# ANS_1_1.net
KiCad netlist of a schematic drawn in EAGLE
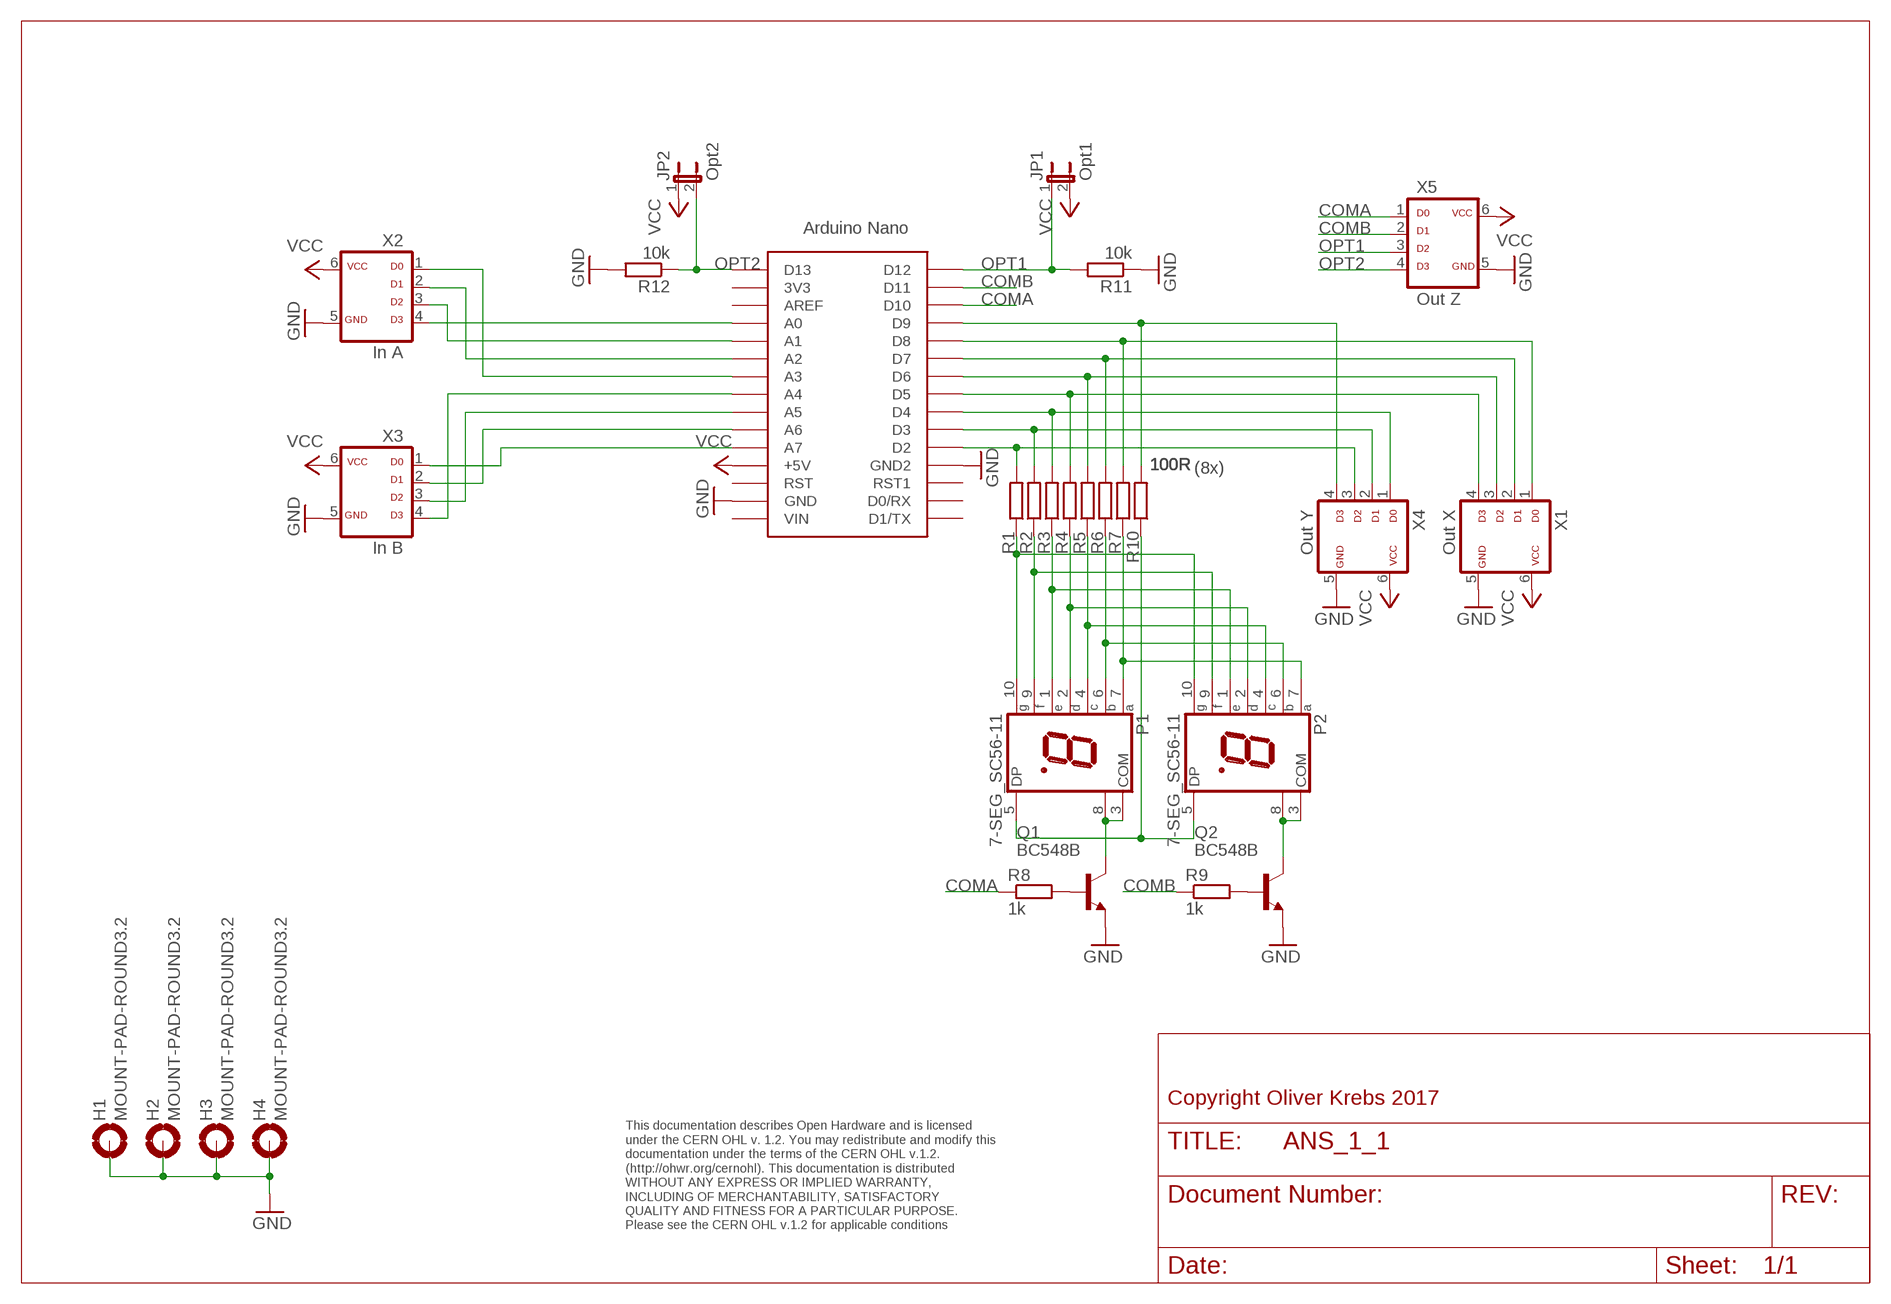
[diagram p0: schematic, sheet 1]

(export (version "E")
  (design (tool "Eeschema 10.0.6"))
  (components
    (comp (ref "H1")
      (value "MOUNT-PAD-ROUND3.2")
      (footprint "eagle-import:3,2-PAD")
      (libsource (lib "eagle-import") (part "MOUNT-PAD-ROUND3.2"))
    )
    (comp (ref "H2")
      (value "MOUNT-PAD-ROUND3.2")
      (footprint "eagle-import:3,2-PAD")
      (libsource (lib "eagle-import") (part "MOUNT-PAD-ROUND3.2"))
    )
    (comp (ref "H3")
      (value "MOUNT-PAD-ROUND3.2")
      (footprint "eagle-import:3,2-PAD")
      (libsource (lib "eagle-import") (part "MOUNT-PAD-ROUND3.2"))
    )
    (comp (ref "H4")
      (value "MOUNT-PAD-ROUND3.2")
      (footprint "eagle-import:3,2-PAD")
      (libsource (lib "eagle-import") (part "MOUNT-PAD-ROUND3.2"))
    )
    (comp (ref "JP1")
      (value "Opt1")
      (footprint "eagle-import:JP1")
      (libsource (lib "eagle-import") (part "JP1E"))
    )
    (comp (ref "JP2")
      (value "Opt2")
      (footprint "eagle-import:JP1")
      (libsource (lib "eagle-import") (part "JP1E"))
    )
    (comp (ref "P1")
      (value "7-SEG_SC56-11")
      (footprint "eagle-import:SA56-11")
      (libsource (lib "eagle-import") (part "7-SEG_SA56-11"))
    )
    (comp (ref "P2")
      (value "7-SEG_SC56-11")
      (footprint "eagle-import:SA56-11")
      (libsource (lib "eagle-import") (part "7-SEG_SA56-11"))
    )
    (comp (ref "Q1")
      (value "BC548B")
      (footprint "eagle-import:TO92-EBC")
      (libsource (lib "eagle-import") (part "BC548B"))
    )
    (comp (ref "Q2")
      (value "BC548B")
      (footprint "eagle-import:TO92-EBC")
      (libsource (lib "eagle-import") (part "BC548B"))
    )
    (comp (ref "R1")
      (value "100R")
      (footprint "eagle-import:0207_10")
      (libsource (lib "eagle-import") (part "R-EU_0207/10"))
    )
    (comp (ref "R2")
      (value "100R")
      (footprint "eagle-import:0207_10")
      (libsource (lib "eagle-import") (part "R-EU_0207/10"))
    )
    (comp (ref "R3")
      (value "100R")
      (footprint "eagle-import:0207_10")
      (libsource (lib "eagle-import") (part "R-EU_0207/10"))
    )
    (comp (ref "R4")
      (value "100R")
      (footprint "eagle-import:0207_10")
      (libsource (lib "eagle-import") (part "R-EU_0207/10"))
    )
    (comp (ref "R5")
      (value "100R")
      (footprint "eagle-import:0207_10")
      (libsource (lib "eagle-import") (part "R-EU_0207/10"))
    )
    (comp (ref "R6")
      (value "100R")
      (footprint "eagle-import:0207_10")
      (libsource (lib "eagle-import") (part "R-EU_0207/10"))
    )
    (comp (ref "R7")
      (value "100R")
      (footprint "eagle-import:0207_10")
      (libsource (lib "eagle-import") (part "R-EU_0207/10"))
    )
    (comp (ref "R8")
      (value "1k")
      (footprint "eagle-import:0207_10")
      (libsource (lib "eagle-import") (part "R-EU_0207/10"))
    )
    (comp (ref "R9")
      (value "1k")
      (footprint "eagle-import:0207_10")
      (libsource (lib "eagle-import") (part "R-EU_0207/10"))
    )
    (comp (ref "R10")
      (value "100R")
      (footprint "eagle-import:0207_10")
      (libsource (lib "eagle-import") (part "R-EU_0207/10"))
    )
    (comp (ref "R11")
      (value "10k")
      (footprint "eagle-import:0207_10")
      (libsource (lib "eagle-import") (part "R-EU_0207/10"))
    )
    (comp (ref "R12")
      (value "10k")
      (footprint "eagle-import:0207_10")
      (libsource (lib "eagle-import") (part "R-EU_0207/10"))
    )
    (comp (ref "U$1")
      (value "NANO")
      (footprint "eagle-import:NANO")
      (libsource (lib "eagle-import") (part "NANO"))
    )
    (comp (ref "X1")
      (value "Out X")
      (footprint "eagle-import:ML-6")
      (libsource (lib "eagle-import") (part "ML6D"))
    )
    (comp (ref "X2")
      (value "In A")
      (footprint "eagle-import:ML-6")
      (libsource (lib "eagle-import") (part "ML6D"))
    )
    (comp (ref "X3")
      (value "In B")
      (footprint "eagle-import:ML-6")
      (libsource (lib "eagle-import") (part "ML6D"))
    )
    (comp (ref "X4")
      (value "Out Y")
      (footprint "eagle-import:ML-6")
      (libsource (lib "eagle-import") (part "ML6D"))
    )
    (comp (ref "X5")
      (value "Out Z")
      (footprint "eagle-import:ML-6")
      (libsource (lib "eagle-import") (part "ML6D"))
    )
  )
  (nets
    (net (code "1") (name "/COMA") (class "Default")
      (node (ref "R8") (pin "1") (pinfunction "1_1") (pintype "passive"))
      (node (ref "U$1") (pin "D10") (pinfunction "D10_D10") (pintype "bidirectional"))
      (node (ref "X5") (pin "1") (pinfunction "1_1") (pintype "passive"))
    )
    (net (code "2") (name "/COMB") (class "Default")
      (node (ref "R9") (pin "1") (pinfunction "1_1") (pintype "passive"))
      (node (ref "U$1") (pin "D11") (pinfunction "D11_D11") (pintype "bidirectional"))
      (node (ref "X5") (pin "2") (pinfunction "2_2") (pintype "passive"))
    )
    (net (code "3") (name "/OPT1") (class "Default")
      (node (ref "JP1") (pin "1") (pinfunction "1_1") (pintype "passive"))
      (node (ref "R11") (pin "2") (pinfunction "2_2") (pintype "passive"))
      (node (ref "U$1") (pin "D12") (pinfunction "D12_D12") (pintype "bidirectional"))
      (node (ref "X5") (pin "3") (pinfunction "3_3") (pintype "passive"))
    )
    (net (code "4") (name "/OPT2") (class "Default")
      (node (ref "JP2") (pin "2") (pinfunction "2_2") (pintype "passive"))
      (node (ref "R12") (pin "1") (pinfunction "1_1") (pintype "passive"))
      (node (ref "U$1") (pin "D13") (pinfunction "D13_D13") (pintype "bidirectional"))
      (node (ref "X5") (pin "4") (pinfunction "4_4") (pintype "passive"))
    )
    (net (code "5") (name "GND") (class "Default")
      (node (ref "H1") (pin "B3,2") (pinfunction "MOUNT_B3,2") (pintype "passive"))
      (node (ref "H2") (pin "B3,2") (pinfunction "MOUNT_B3,2") (pintype "passive"))
      (node (ref "H3") (pin "B3,2") (pinfunction "MOUNT_B3,2") (pintype "passive"))
      (node (ref "H4") (pin "B3,2") (pinfunction "MOUNT_B3,2") (pintype "passive"))
      (node (ref "Q1") (pin "E") (pinfunction "E_E") (pintype "passive"))
      (node (ref "Q2") (pin "E") (pinfunction "E_E") (pintype "passive"))
      (node (ref "R11") (pin "1") (pinfunction "1_1") (pintype "passive"))
      (node (ref "R12") (pin "2") (pinfunction "2_2") (pintype "passive"))
      (node (ref "U$1") (pin "GND") (pinfunction "GND_GND") (pintype "bidirectional"))
      (node (ref "U$1") (pin "GND1") (pinfunction "GND2_GND1") (pintype "bidirectional"))
      (node (ref "X1") (pin "5") (pinfunction "5_5") (pintype "passive"))
      (node (ref "X2") (pin "5") (pinfunction "5_5") (pintype "passive"))
      (node (ref "X3") (pin "5") (pinfunction "5_5") (pintype "passive"))
      (node (ref "X4") (pin "5") (pinfunction "5_5") (pintype "passive"))
      (node (ref "X5") (pin "5") (pinfunction "5_5") (pintype "passive"))
    )
    (net (code "6") (name "Net-(P1-A)") (class "Default")
      (node (ref "P1") (pin "7") (pinfunction "A_7") (pintype "passive"))
      (node (ref "P2") (pin "7") (pinfunction "A_7") (pintype "passive"))
      (node (ref "R7") (pin "1") (pinfunction "1_1") (pintype "passive"))
    )
    (net (code "7") (name "Net-(P1-B)") (class "Default")
      (node (ref "P1") (pin "6") (pinfunction "B_6") (pintype "passive"))
      (node (ref "P2") (pin "6") (pinfunction "B_6") (pintype "passive"))
      (node (ref "R6") (pin "1") (pinfunction "1_1") (pintype "passive"))
    )
    (net (code "8") (name "Net-(P1-C)") (class "Default")
      (node (ref "P1") (pin "4") (pinfunction "C_4") (pintype "passive"))
      (node (ref "P2") (pin "4") (pinfunction "C_4") (pintype "passive"))
      (node (ref "R5") (pin "1") (pinfunction "1_1") (pintype "passive"))
    )
    (net (code "9") (name "Net-(P1-COM-Pad3)") (class "Default")
      (node (ref "P1") (pin "3") (pinfunction "COM_3") (pintype "passive"))
      (node (ref "P1") (pin "8") (pinfunction "COM_8") (pintype "passive"))
      (node (ref "Q1") (pin "C") (pinfunction "C_C") (pintype "passive"))
    )
    (net (code "10") (name "Net-(P1-D)") (class "Default")
      (node (ref "P1") (pin "2") (pinfunction "D_2") (pintype "passive"))
      (node (ref "P2") (pin "2") (pinfunction "D_2") (pintype "passive"))
      (node (ref "R4") (pin "1") (pinfunction "1_1") (pintype "passive"))
    )
    (net (code "11") (name "Net-(P1-DP)") (class "Default")
      (node (ref "P1") (pin "5") (pinfunction "DP_5") (pintype "passive"))
      (node (ref "P2") (pin "5") (pinfunction "DP_5") (pintype "passive"))
      (node (ref "R10") (pin "1") (pinfunction "1_1") (pintype "passive"))
    )
    (net (code "12") (name "Net-(P1-E)") (class "Default")
      (node (ref "P1") (pin "1") (pinfunction "E_1") (pintype "passive"))
      (node (ref "P2") (pin "1") (pinfunction "E_1") (pintype "passive"))
      (node (ref "R3") (pin "1") (pinfunction "1_1") (pintype "passive"))
    )
    (net (code "13") (name "Net-(P1-F)") (class "Default")
      (node (ref "P1") (pin "9") (pinfunction "F_9") (pintype "passive"))
      (node (ref "P2") (pin "9") (pinfunction "F_9") (pintype "passive"))
      (node (ref "R2") (pin "1") (pinfunction "1_1") (pintype "passive"))
    )
    (net (code "14") (name "Net-(P1-G)") (class "Default")
      (node (ref "P1") (pin "10") (pinfunction "G_10") (pintype "passive"))
      (node (ref "P2") (pin "10") (pinfunction "G_10") (pintype "passive"))
      (node (ref "R1") (pin "1") (pinfunction "1_1") (pintype "passive"))
    )
    (net (code "15") (name "Net-(P2-COM-Pad3)") (class "Default")
      (node (ref "P2") (pin "3") (pinfunction "COM_3") (pintype "passive"))
      (node (ref "P2") (pin "8") (pinfunction "COM_8") (pintype "passive"))
      (node (ref "Q2") (pin "C") (pinfunction "C_C") (pintype "passive"))
    )
    (net (code "16") (name "Net-(Q1-PadB)") (class "Default")
      (node (ref "Q1") (pin "B") (pinfunction "B_B") (pintype "passive"))
      (node (ref "R8") (pin "2") (pinfunction "2_2") (pintype "passive"))
    )
    (net (code "17") (name "Net-(Q2-PadB)") (class "Default")
      (node (ref "Q2") (pin "B") (pinfunction "B_B") (pintype "passive"))
      (node (ref "R9") (pin "2") (pinfunction "2_2") (pintype "passive"))
    )
    (net (code "18") (name "Net-(R1-Pad2)") (class "Default")
      (node (ref "R1") (pin "2") (pinfunction "2_2") (pintype "passive"))
      (node (ref "U$1") (pin "D2") (pinfunction "D2_D2") (pintype "bidirectional"))
      (node (ref "X4") (pin "3") (pinfunction "3_3") (pintype "passive"))
    )
    (net (code "19") (name "Net-(R2-Pad2)") (class "Default")
      (node (ref "R2") (pin "2") (pinfunction "2_2") (pintype "passive"))
      (node (ref "U$1") (pin "D3") (pinfunction "D3_D3") (pintype "bidirectional"))
      (node (ref "X4") (pin "2") (pinfunction "2_2") (pintype "passive"))
    )
    (net (code "20") (name "Net-(R3-Pad2)") (class "Default")
      (node (ref "R3") (pin "2") (pinfunction "2_2") (pintype "passive"))
      (node (ref "U$1") (pin "D4") (pinfunction "D4_D4") (pintype "bidirectional"))
      (node (ref "X4") (pin "1") (pinfunction "1_1") (pintype "passive"))
    )
    (net (code "21") (name "Net-(R4-Pad2)") (class "Default")
      (node (ref "R4") (pin "2") (pinfunction "2_2") (pintype "passive"))
      (node (ref "U$1") (pin "D5") (pinfunction "D5_D5") (pintype "bidirectional"))
      (node (ref "X1") (pin "4") (pinfunction "4_4") (pintype "passive"))
    )
    (net (code "22") (name "Net-(R5-Pad2)") (class "Default")
      (node (ref "R5") (pin "2") (pinfunction "2_2") (pintype "passive"))
      (node (ref "U$1") (pin "D6") (pinfunction "D6_D6") (pintype "bidirectional"))
      (node (ref "X1") (pin "3") (pinfunction "3_3") (pintype "passive"))
    )
    (net (code "23") (name "Net-(R6-Pad2)") (class "Default")
      (node (ref "R6") (pin "2") (pinfunction "2_2") (pintype "passive"))
      (node (ref "U$1") (pin "D7") (pinfunction "D7_D7") (pintype "bidirectional"))
      (node (ref "X1") (pin "2") (pinfunction "2_2") (pintype "passive"))
    )
    (net (code "24") (name "Net-(R7-Pad2)") (class "Default")
      (node (ref "R7") (pin "2") (pinfunction "2_2") (pintype "passive"))
      (node (ref "U$1") (pin "D8") (pinfunction "D8_D8") (pintype "bidirectional"))
      (node (ref "X1") (pin "1") (pinfunction "1_1") (pintype "passive"))
    )
    (net (code "25") (name "Net-(R10-Pad2)") (class "Default")
      (node (ref "R10") (pin "2") (pinfunction "2_2") (pintype "passive"))
      (node (ref "U$1") (pin "D9") (pinfunction "D9_D9") (pintype "bidirectional"))
      (node (ref "X4") (pin "4") (pinfunction "4_4") (pintype "passive"))
    )
    (net (code "26") (name "Net-(U$1-PadA0)") (class "Default")
      (node (ref "U$1") (pin "A0") (pinfunction "A0_A0") (pintype "bidirectional"))
      (node (ref "X2") (pin "4") (pinfunction "4_4") (pintype "passive"))
    )
    (net (code "27") (name "Net-(U$1-PadA1)") (class "Default")
      (node (ref "U$1") (pin "A1") (pinfunction "A1_A1") (pintype "bidirectional"))
      (node (ref "X2") (pin "3") (pinfunction "3_3") (pintype "passive"))
    )
    (net (code "28") (name "Net-(U$1-PadA2)") (class "Default")
      (node (ref "U$1") (pin "A2") (pinfunction "A2_A2") (pintype "bidirectional"))
      (node (ref "X2") (pin "2") (pinfunction "2_2") (pintype "passive"))
    )
    (net (code "29") (name "Net-(U$1-PadA3)") (class "Default")
      (node (ref "U$1") (pin "A3") (pinfunction "A3_A3") (pintype "bidirectional"))
      (node (ref "X2") (pin "1") (pinfunction "1_1") (pintype "passive"))
    )
    (net (code "30") (name "Net-(U$1-PadA4)") (class "Default")
      (node (ref "U$1") (pin "A4") (pinfunction "A4_A4") (pintype "bidirectional"))
      (node (ref "X3") (pin "4") (pinfunction "4_4") (pintype "passive"))
    )
    (net (code "31") (name "Net-(U$1-PadA5)") (class "Default")
      (node (ref "U$1") (pin "A5") (pinfunction "A5_A5") (pintype "bidirectional"))
      (node (ref "X3") (pin "3") (pinfunction "3_3") (pintype "passive"))
    )
    (net (code "32") (name "Net-(U$1-PadA6)") (class "Default")
      (node (ref "U$1") (pin "A6") (pinfunction "A6_A6") (pintype "bidirectional"))
      (node (ref "X3") (pin "2") (pinfunction "2_2") (pintype "passive"))
    )
    (net (code "33") (name "Net-(U$1-PadA7)") (class "Default")
      (node (ref "U$1") (pin "A7") (pinfunction "A7_A7") (pintype "bidirectional"))
      (node (ref "X3") (pin "1") (pinfunction "1_1") (pintype "passive"))
    )
    (net (code "34") (name "VCC") (class "Default")
      (node (ref "JP1") (pin "2") (pinfunction "2_2") (pintype "passive"))
      (node (ref "JP2") (pin "1") (pinfunction "1_1") (pintype "passive"))
      (node (ref "U$1") (pin "5V") (pinfunction "+5V_5V") (pintype "bidirectional"))
      (node (ref "X1") (pin "6") (pinfunction "6_6") (pintype "passive"))
      (node (ref "X2") (pin "6") (pinfunction "6_6") (pintype "passive"))
      (node (ref "X3") (pin "6") (pinfunction "6_6") (pintype "passive"))
      (node (ref "X4") (pin "6") (pinfunction "6_6") (pintype "passive"))
      (node (ref "X5") (pin "6") (pinfunction "6_6") (pintype "passive"))
    )
    (net (code "35") (name "unconnected-(U$1-3V3-Pad3.3V)") (class "Default")
      (node (ref "U$1") (pin "3.3V") (pinfunction "3V3_3.3V") (pintype "bidirectional"))
    )
    (net (code "36") (name "unconnected-(U$1-D0{slash}RX-PadRX1)") (class "Default")
      (node (ref "U$1") (pin "RX1") (pinfunction "D0/RX_RX1") (pintype "bidirectional"))
    )
    (net (code "37") (name "unconnected-(U$1-D1{slash}TX-PadTX0)") (class "Default")
      (node (ref "U$1") (pin "TX0") (pinfunction "D1/TX_TX0") (pintype "bidirectional"))
    )
    (net (code "38") (name "unconnected-(U$1-PadAREF)") (class "Default")
      (node (ref "U$1") (pin "AREF") (pinfunction "AREF_AREF") (pintype "bidirectional"))
    )
    (net (code "39") (name "unconnected-(U$1-PadRST)") (class "Default")
      (node (ref "U$1") (pin "RST") (pinfunction "RST_RST") (pintype "bidirectional"))
    )
    (net (code "40") (name "unconnected-(U$1-PadRST1)") (class "Default")
      (node (ref "U$1") (pin "RST1") (pinfunction "RST1_RST1") (pintype "bidirectional"))
    )
    (net (code "41") (name "unconnected-(U$1-VIN-PadRAW)") (class "Default")
      (node (ref "U$1") (pin "RAW") (pinfunction "VIN_RAW") (pintype "bidirectional"))
    )
  )
)
